# SPWF04SA-v1_0_0.net
KiCad netlist of a schematic drawn in EAGLE
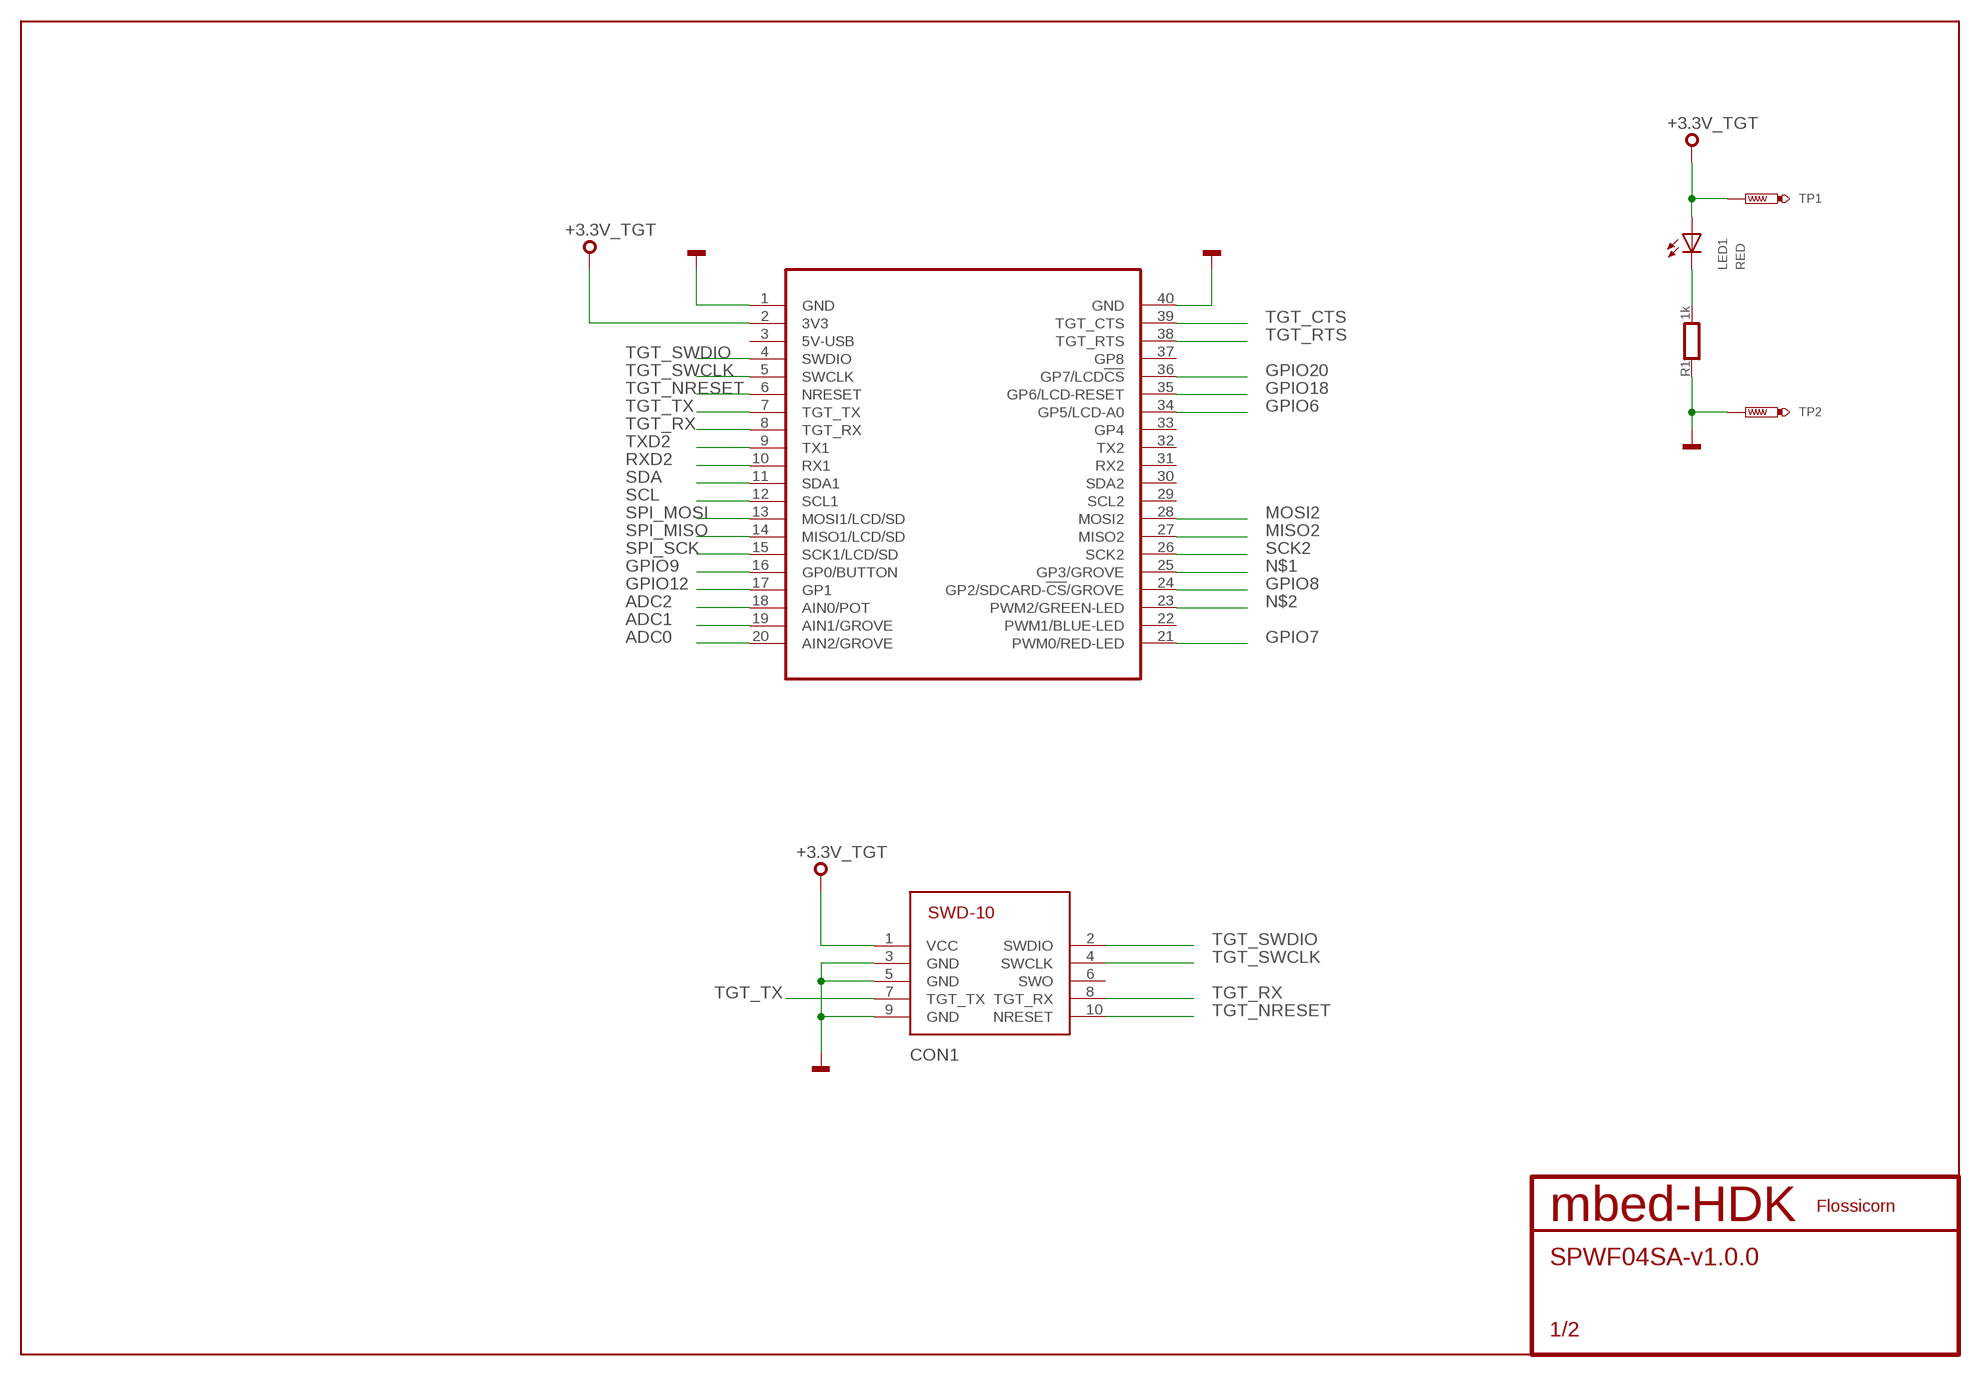
[diagram p0: schematic, sheet 1]
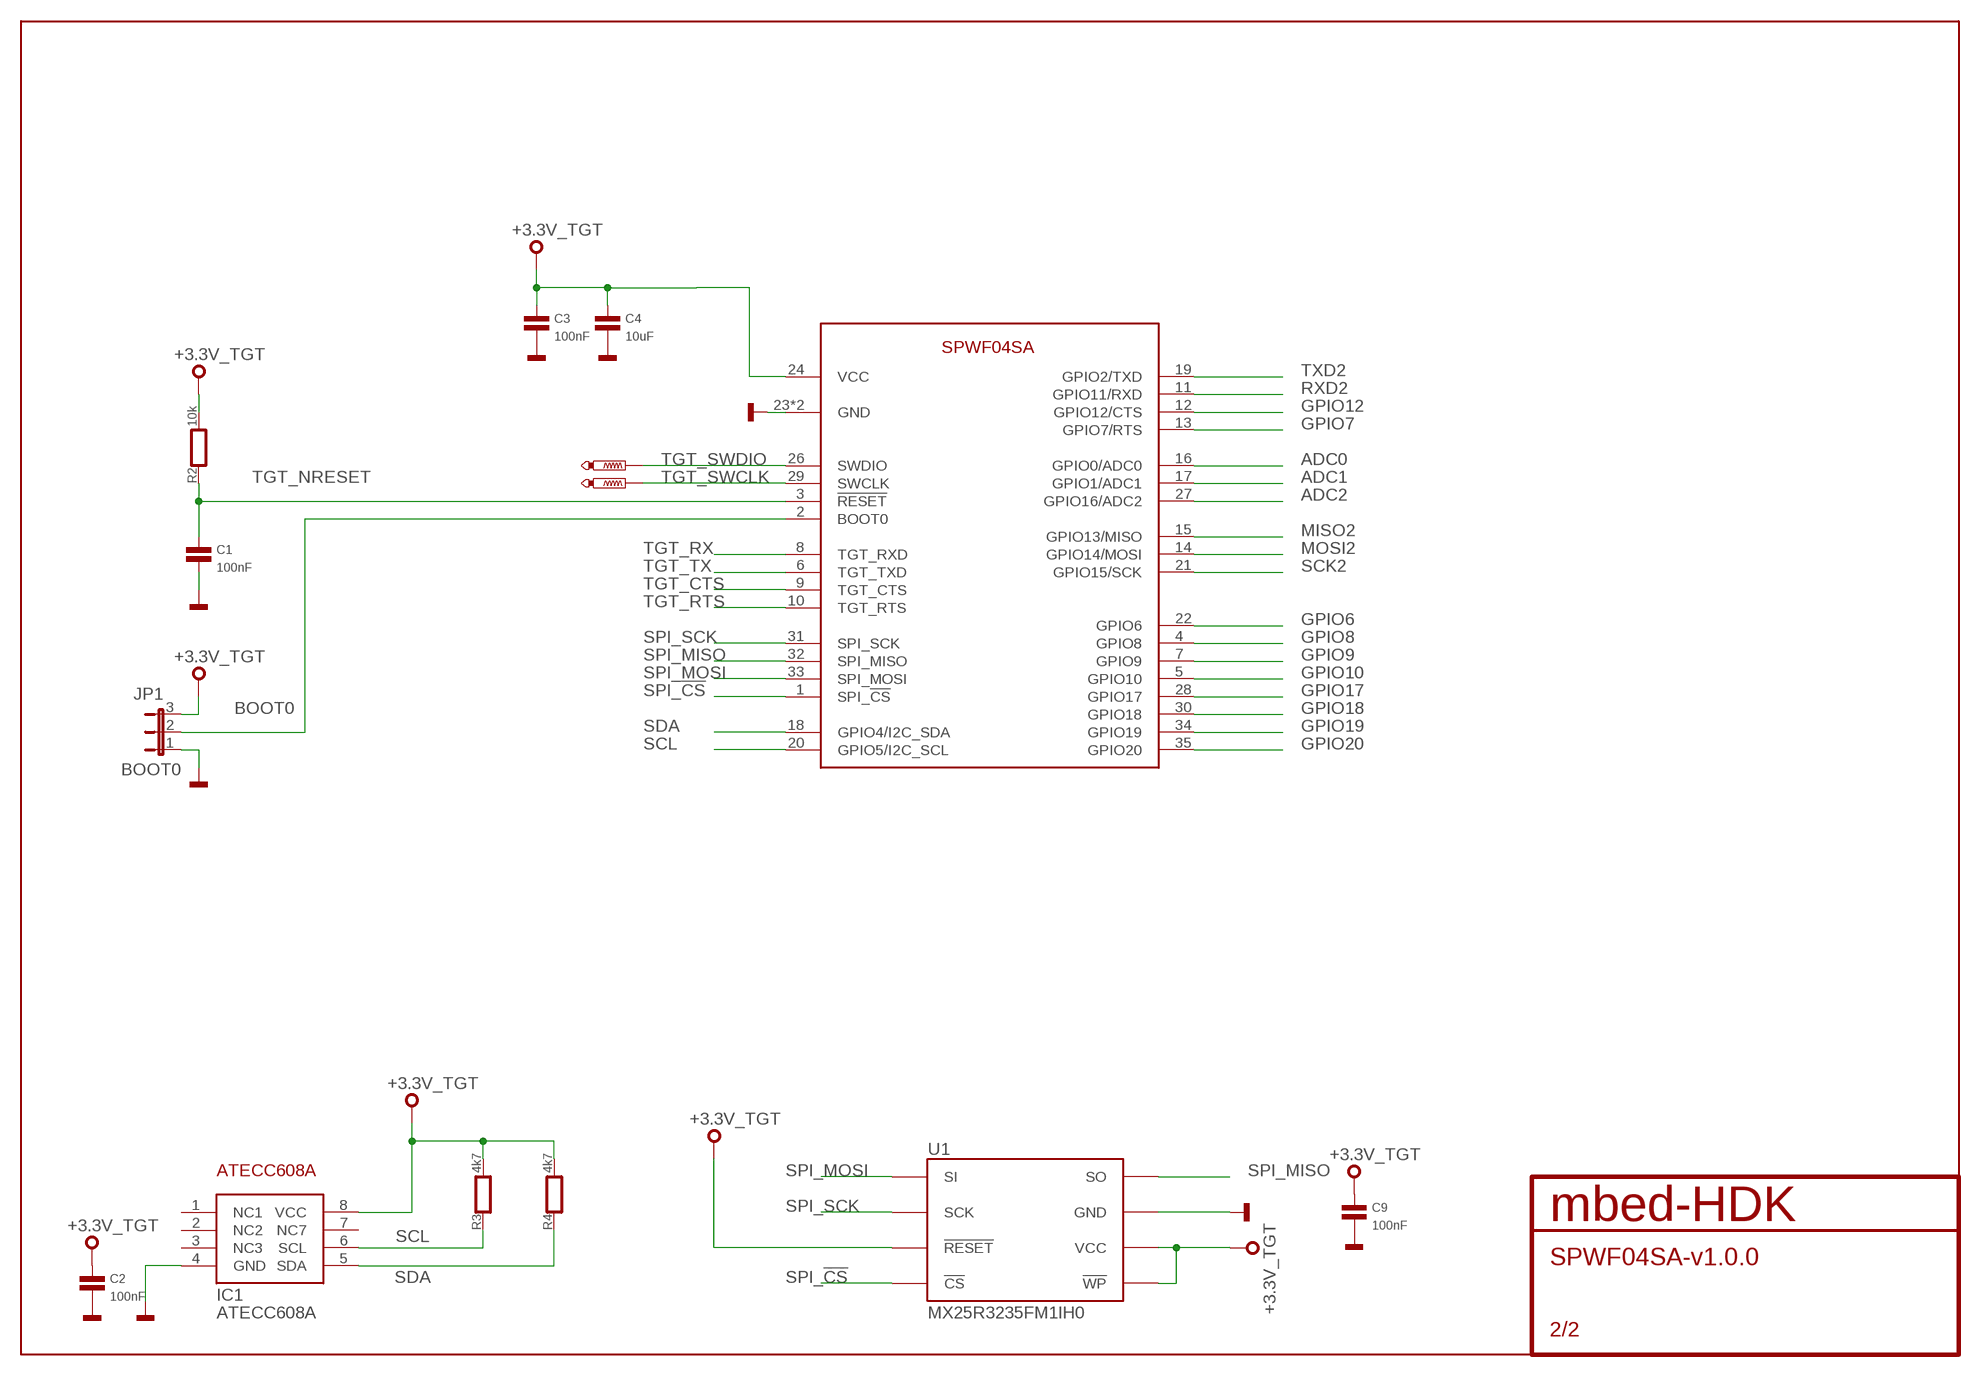
[diagram p1: schematic, sheet 2]

(export (version "E")
  (design (tool "Eeschema 10.0.6"))
  (components
    (comp (ref "C1")
      (value "100nF")
      (footprint "eagle-import:0603")
      (libsource (lib "eagle-import") (part "CAPACITOR0603"))
    )
    (comp (ref "C2")
      (value "100nF")
      (footprint "eagle-import:0603")
      (libsource (lib "eagle-import") (part "CAPACITOR0603"))
    )
    (comp (ref "C3")
      (value "100nF")
      (footprint "eagle-import:0603")
      (libsource (lib "eagle-import") (part "CAPACITOR0603"))
    )
    (comp (ref "C4")
      (value "10uF")
      (footprint "eagle-import:0603")
      (libsource (lib "eagle-import") (part "CAPACITOR0603"))
    )
    (comp (ref "C9")
      (value "100nF")
      (footprint "eagle-import:0603")
      (libsource (lib "eagle-import") (part "CAPACITOR0603"))
    )
    (comp (ref "IC1")
      (value "ATECC608A")
      (footprint "eagle-import:SO8")
      (libsource (lib "eagle-import") (part "ATECC608A"))
    )
    (comp (ref "JP1")
      (value "BOOT0")
      (footprint "eagle-import:JP2")
      (libsource (lib "eagle-import") (part "JP2E"))
    )
    (comp (ref "MOD2")
      (value "SPWF04SA")
      (footprint "eagle-import:SPWF04SA")
      (libsource (lib "eagle-import") (part "SPWF04SA"))
    )
    (comp (ref "R2")
      (value "10k")
      (footprint "eagle-import:0603")
      (libsource (lib "eagle-import") (part "RESISTOR0603"))
    )
    (comp (ref "R3")
      (value "4k7")
      (footprint "eagle-import:0603")
      (libsource (lib "eagle-import") (part "RESISTOR0603"))
    )
    (comp (ref "R4")
      (value "4k7")
      (footprint "eagle-import:0603")
      (libsource (lib "eagle-import") (part "RESISTOR0603"))
    )
    (comp (ref "TP3")
      (value "PTR1TP10R")
      (footprint "eagle-import:TP10R")
      (libsource (lib "eagle-import") (part "PTR1TP10R"))
    )
    (comp (ref "TP4")
      (value "PTR1TP10R")
      (footprint "eagle-import:TP10R")
      (libsource (lib "eagle-import") (part "PTR1TP10R"))
    )
    (comp (ref "U1")
      (value "MX25R3235FM1IH0")
      (footprint "eagle-import:SO8")
      (fields (field (name "MF") "Macronix"))
      (libsource (lib "eagle-import") (part "MX25R3235FM1IH0"))
    )
    (comp (ref "CON1")
      (value "SWD-10/TC2050_SMD")
      (footprint "eagle-import:FTSH-105-02")
      (libsource (lib "eagle-import") (part "SWD-10/TC2050_SMD"))
    )
    (comp (ref "LED1")
      (value "RED")
      (footprint "eagle-import:CHIPLED_0603")
      (fields (field (name "MF") "Wurth Electronics Inc"))
      (libsource (lib "eagle-import") (part "SMD_LED0603"))
    )
    (comp (ref "MOD1")
      (value "MODULE_DAUGHTER")
      (footprint "eagle-import:MODULE_DAUGHTER")
      (libsource (lib "eagle-import") (part "MODULE_DAUGHTER"))
    )
    (comp (ref "R1")
      (value "1k")
      (footprint "eagle-import:0603")
      (libsource (lib "eagle-import") (part "RESISTOR0603"))
    )
    (comp (ref "SS1")
      (value "FLOSSICORN0.5")
      (footprint "eagle-import:FLOSSICORN-0.5")
      (libsource (lib "eagle-import") (part "FLOSSICORN0.5"))
    )
    (comp (ref "TP1")
      (value "TEST-POINT-50R-PTH")
      (footprint "eagle-import:TP50-PTH")
      (libsource (lib "eagle-import") (part "TEST-POINT-50R-PTH"))
    )
    (comp (ref "TP2")
      (value "TEST-POINT-50R-PTH")
      (footprint "eagle-import:TP50-PTH")
      (libsource (lib "eagle-import") (part "TEST-POINT-50R-PTH"))
    )
  )
  (nets
    (net (code "1") (name "+3.3V_TGT") (class "Default")
      (node (ref "C2") (pin "1") (pinfunction "P$1_1") (pintype "passive"))
      (node (ref "C3") (pin "1") (pinfunction "P$1_1") (pintype "passive"))
      (node (ref "C4") (pin "1") (pinfunction "P$1_1") (pintype "passive"))
      (node (ref "C9") (pin "1") (pinfunction "P$1_1") (pintype "passive"))
      (node (ref "CON1") (pin "1") (pinfunction "VCC_1") (pintype "bidirectional"))
      (node (ref "IC1") (pin "8") (pinfunction "VCC_8") (pintype "bidirectional"))
      (node (ref "JP1") (pin "3") (pinfunction "3_3") (pintype "passive"))
      (node (ref "LED1") (pin "A") (pinfunction "A_A") (pintype "passive"))
      (node (ref "MOD1") (pin "2") (pinfunction "3V3_2") (pintype "bidirectional"))
      (node (ref "MOD2") (pin "24") (pinfunction "VCC_24") (pintype "bidirectional"))
      (node (ref "R2") (pin "2") (pinfunction "P$2_2") (pintype "passive"))
      (node (ref "R3") (pin "2") (pinfunction "P$2_2") (pintype "passive"))
      (node (ref "R4") (pin "2") (pinfunction "P$2_2") (pintype "passive"))
      (node (ref "TP1") (pin "TP") (pinfunction "TP_TP") (pintype "input"))
      (node (ref "U1") (pin "3") (pinfunction "~{WP}_3") (pintype "bidirectional"))
      (node (ref "U1") (pin "7") (pinfunction "~{RESET}_7") (pintype "bidirectional"))
      (node (ref "U1") (pin "8") (pinfunction "VCC_8") (pintype "bidirectional"))
    )
    (net (code "2") (name "ADC0") (class "Default")
      (node (ref "MOD1") (pin "20") (pinfunction "AIN2/GROVE_20") (pintype "bidirectional"))
      (node (ref "MOD2") (pin "16") (pinfunction "GPIO0/ADC0_16") (pintype "bidirectional"))
    )
    (net (code "3") (name "ADC1") (class "Default")
      (node (ref "MOD1") (pin "19") (pinfunction "AIN1/GROVE_19") (pintype "bidirectional"))
      (node (ref "MOD2") (pin "17") (pinfunction "GPIO1/ADC1_17") (pintype "bidirectional"))
    )
    (net (code "4") (name "ADC2") (class "Default")
      (node (ref "MOD1") (pin "18") (pinfunction "AIN0/POT_18") (pintype "bidirectional"))
      (node (ref "MOD2") (pin "27") (pinfunction "GPIO16/ADC2_27") (pintype "bidirectional"))
    )
    (net (code "5") (name "BOOT0") (class "Default")
      (node (ref "JP1") (pin "2") (pinfunction "2_2") (pintype "passive"))
      (node (ref "MOD2") (pin "2") (pinfunction "BOOT0_2") (pintype "bidirectional"))
    )
    (net (code "6") (name "GND") (class "Default")
      (node (ref "C1") (pin "2") (pinfunction "P$2_2") (pintype "passive"))
      (node (ref "C2") (pin "2") (pinfunction "P$2_2") (pintype "passive"))
      (node (ref "C3") (pin "2") (pinfunction "P$2_2") (pintype "passive"))
      (node (ref "C4") (pin "2") (pinfunction "P$2_2") (pintype "passive"))
      (node (ref "C9") (pin "2") (pinfunction "P$2_2") (pintype "passive"))
      (node (ref "CON1") (pin "3") (pinfunction "GND_3") (pintype "bidirectional"))
      (node (ref "CON1") (pin "5") (pinfunction "GND_5") (pintype "bidirectional"))
      (node (ref "CON1") (pin "9") (pinfunction "GND_9") (pintype "bidirectional"))
      (node (ref "IC1") (pin "4") (pinfunction "GND_4") (pintype "bidirectional"))
      (node (ref "JP1") (pin "1") (pinfunction "1_1") (pintype "passive"))
      (node (ref "MOD1") (pin "1") (pinfunction "GND_1") (pintype "bidirectional"))
      (node (ref "MOD1") (pin "40") (pinfunction "GND_40") (pintype "bidirectional"))
      (node (ref "MOD2") (pin "23") (pinfunction "GND_23") (pintype "bidirectional"))
      (node (ref "MOD2") (pin "25") (pinfunction "GND_25") (pintype "bidirectional"))
      (node (ref "R1") (pin "1") (pinfunction "P$1_1") (pintype "passive"))
      (node (ref "TP2") (pin "TP") (pinfunction "TP_TP") (pintype "input"))
      (node (ref "U1") (pin "4") (pinfunction "GND_4") (pintype "bidirectional"))
    )
    (net (code "7") (name "GPIO6") (class "Default")
      (node (ref "MOD1") (pin "34") (pinfunction "GP5/LCD-A0_34") (pintype "bidirectional"))
      (node (ref "MOD2") (pin "22") (pinfunction "GPIO6_22") (pintype "bidirectional"))
    )
    (net (code "8") (name "GPIO7") (class "Default")
      (node (ref "MOD1") (pin "21") (pinfunction "PWM0/RED-LED_21") (pintype "bidirectional"))
      (node (ref "MOD2") (pin "13") (pinfunction "GPIO7/RTS_13") (pintype "bidirectional"))
    )
    (net (code "9") (name "GPIO8") (class "Default")
      (node (ref "MOD1") (pin "24") (pinfunction "GP2/SDCARD-~{CS}/GROVE_24") (pintype "bidirectional"))
      (node (ref "MOD2") (pin "4") (pinfunction "GPIO8_4") (pintype "bidirectional"))
    )
    (net (code "10") (name "GPIO9") (class "Default")
      (node (ref "MOD1") (pin "16") (pinfunction "GP0/BUTTON_16") (pintype "bidirectional"))
      (node (ref "MOD2") (pin "7") (pinfunction "GPIO9_7") (pintype "bidirectional"))
    )
    (net (code "11") (name "GPIO10") (class "Default")
      (node (ref "MOD2") (pin "5") (pinfunction "GPIO10_5") (pintype "bidirectional"))
    )
    (net (code "12") (name "GPIO12") (class "Default")
      (node (ref "MOD1") (pin "17") (pinfunction "GP1_17") (pintype "bidirectional"))
      (node (ref "MOD2") (pin "12") (pinfunction "GPIO12/CTS_12") (pintype "bidirectional"))
    )
    (net (code "13") (name "GPIO17") (class "Default")
      (node (ref "MOD2") (pin "28") (pinfunction "GPIO17_28") (pintype "bidirectional"))
    )
    (net (code "14") (name "GPIO18") (class "Default")
      (node (ref "MOD1") (pin "35") (pinfunction "GP6/LCD-RESET_35") (pintype "bidirectional"))
      (node (ref "MOD2") (pin "30") (pinfunction "GPIO18_30") (pintype "bidirectional"))
    )
    (net (code "15") (name "GPIO19") (class "Default")
      (node (ref "MOD2") (pin "34") (pinfunction "GPIO19_34") (pintype "bidirectional"))
    )
    (net (code "16") (name "GPIO20") (class "Default")
      (node (ref "MOD1") (pin "36") (pinfunction "GP7/LCD~{CS}_36") (pintype "bidirectional"))
      (node (ref "MOD2") (pin "35") (pinfunction "GPIO20_35") (pintype "bidirectional"))
    )
    (net (code "17") (name "MISO2") (class "Default")
      (node (ref "MOD1") (pin "27") (pinfunction "MISO2_27") (pintype "bidirectional"))
      (node (ref "MOD2") (pin "15") (pinfunction "GPIO13/MISO_15") (pintype "bidirectional"))
    )
    (net (code "18") (name "MOSI2") (class "Default")
      (node (ref "MOD1") (pin "28") (pinfunction "MOSI2_28") (pintype "bidirectional"))
      (node (ref "MOD2") (pin "14") (pinfunction "GPIO14/MOSI_14") (pintype "bidirectional"))
    )
    (net (code "19") (name "N$1") (class "Default")
      (node (ref "MOD1") (pin "25") (pinfunction "GP3/GROVE_25") (pintype "bidirectional"))
    )
    (net (code "20") (name "N$2") (class "Default")
      (node (ref "MOD1") (pin "23") (pinfunction "PWM2/GREEN-LED_23") (pintype "bidirectional"))
    )
    (net (code "21") (name "Net-(R1-P$2)") (class "Default")
      (node (ref "LED1") (pin "C") (pinfunction "C_C") (pintype "passive"))
      (node (ref "R1") (pin "2") (pinfunction "P$2_2") (pintype "passive"))
    )
    (net (code "22") (name "RXD2") (class "Default")
      (node (ref "MOD1") (pin "10") (pinfunction "RX1_10") (pintype "bidirectional"))
      (node (ref "MOD2") (pin "11") (pinfunction "GPIO11/RXD_11") (pintype "bidirectional"))
    )
    (net (code "23") (name "SCK2") (class "Default")
      (node (ref "MOD1") (pin "26") (pinfunction "SCK2_26") (pintype "bidirectional"))
      (node (ref "MOD2") (pin "21") (pinfunction "GPIO15/SCK_21") (pintype "bidirectional"))
    )
    (net (code "24") (name "SCL") (class "Default")
      (node (ref "IC1") (pin "6") (pinfunction "SCL_6") (pintype "bidirectional"))
      (node (ref "MOD1") (pin "12") (pinfunction "SCL1_12") (pintype "bidirectional"))
      (node (ref "MOD2") (pin "20") (pinfunction "GPIO5/I2C_SCL_20") (pintype "bidirectional"))
      (node (ref "R3") (pin "1") (pinfunction "P$1_1") (pintype "passive"))
    )
    (net (code "25") (name "SDA") (class "Default")
      (node (ref "IC1") (pin "5") (pinfunction "SDA_5") (pintype "bidirectional"))
      (node (ref "MOD1") (pin "11") (pinfunction "SDA1_11") (pintype "bidirectional"))
      (node (ref "MOD2") (pin "18") (pinfunction "GPIO4/I2C_SDA_18") (pintype "bidirectional"))
      (node (ref "R4") (pin "1") (pinfunction "P$1_1") (pintype "passive"))
    )
    (net (code "26") (name "SPI_MISO") (class "Default")
      (node (ref "MOD1") (pin "14") (pinfunction "MISO1/LCD/SD_14") (pintype "bidirectional"))
      (node (ref "MOD2") (pin "32") (pinfunction "SPI_MISO_32") (pintype "bidirectional"))
      (node (ref "U1") (pin "2") (pinfunction "SO_2") (pintype "bidirectional"))
    )
    (net (code "27") (name "SPI_MOSI") (class "Default")
      (node (ref "MOD1") (pin "13") (pinfunction "MOSI1/LCD/SD_13") (pintype "bidirectional"))
      (node (ref "MOD2") (pin "33") (pinfunction "SPI_MOSI_33") (pintype "bidirectional"))
      (node (ref "U1") (pin "5") (pinfunction "SI_5") (pintype "bidirectional"))
    )
    (net (code "28") (name "SPI_SCK") (class "Default")
      (node (ref "MOD1") (pin "15") (pinfunction "SCK1/LCD/SD_15") (pintype "bidirectional"))
      (node (ref "MOD2") (pin "31") (pinfunction "SPI_SCK_31") (pintype "bidirectional"))
      (node (ref "U1") (pin "6") (pinfunction "SCK_6") (pintype "bidirectional"))
    )
    (net (code "29") (name "SPI_~{CS}") (class "Default")
      (node (ref "MOD2") (pin "1") (pinfunction "SPI_~{CS}_1") (pintype "bidirectional"))
      (node (ref "U1") (pin "1") (pinfunction "~{CS}_1") (pintype "bidirectional"))
    )
    (net (code "30") (name "TGT_CTS") (class "Default")
      (node (ref "MOD1") (pin "39") (pinfunction "TGT_CTS_39") (pintype "bidirectional"))
      (node (ref "MOD2") (pin "9") (pinfunction "TGT_CTS_9") (pintype "bidirectional"))
    )
    (net (code "31") (name "TGT_NRESET") (class "Default")
      (node (ref "C1") (pin "1") (pinfunction "P$1_1") (pintype "passive"))
      (node (ref "CON1") (pin "10") (pinfunction "NRESET_10") (pintype "bidirectional"))
      (node (ref "MOD1") (pin "6") (pinfunction "NRESET_6") (pintype "bidirectional"))
      (node (ref "MOD2") (pin "3") (pinfunction "~{RESET}_3") (pintype "bidirectional"))
      (node (ref "R2") (pin "1") (pinfunction "P$1_1") (pintype "passive"))
    )
    (net (code "32") (name "TGT_RTS") (class "Default")
      (node (ref "MOD1") (pin "38") (pinfunction "TGT_RTS_38") (pintype "bidirectional"))
      (node (ref "MOD2") (pin "10") (pinfunction "TGT_RTS_10") (pintype "bidirectional"))
    )
    (net (code "33") (name "TGT_RX") (class "Default")
      (node (ref "CON1") (pin "8") (pinfunction "TGT_RX_8") (pintype "bidirectional"))
      (node (ref "MOD1") (pin "8") (pinfunction "TGT_RX_8") (pintype "bidirectional"))
      (node (ref "MOD2") (pin "8") (pinfunction "TGT_RXD_8") (pintype "bidirectional"))
    )
    (net (code "34") (name "TGT_SWCLK") (class "Default")
      (node (ref "CON1") (pin "4") (pinfunction "SWCLK_4") (pintype "bidirectional"))
      (node (ref "MOD1") (pin "5") (pinfunction "SWCLK_5") (pintype "bidirectional"))
      (node (ref "MOD2") (pin "29") (pinfunction "SWCLK_29") (pintype "bidirectional"))
      (node (ref "TP4") (pin "TP") (pinfunction "TP_TP") (pintype "input"))
    )
    (net (code "35") (name "TGT_SWDIO") (class "Default")
      (node (ref "CON1") (pin "2") (pinfunction "SWDIO_2") (pintype "bidirectional"))
      (node (ref "MOD1") (pin "4") (pinfunction "SWDIO_4") (pintype "bidirectional"))
      (node (ref "MOD2") (pin "26") (pinfunction "SWDIO_26") (pintype "bidirectional"))
      (node (ref "TP3") (pin "TP") (pinfunction "TP_TP") (pintype "input"))
    )
    (net (code "36") (name "TGT_TX") (class "Default")
      (node (ref "CON1") (pin "7") (pinfunction "TGT_TX_7") (pintype "bidirectional"))
      (node (ref "MOD1") (pin "7") (pinfunction "TGT_TX_7") (pintype "bidirectional"))
      (node (ref "MOD2") (pin "6") (pinfunction "TGT_TXD_6") (pintype "bidirectional"))
    )
    (net (code "37") (name "TXD2") (class "Default")
      (node (ref "MOD1") (pin "9") (pinfunction "TX1_9") (pintype "bidirectional"))
      (node (ref "MOD2") (pin "19") (pinfunction "GPIO2/TXD_19") (pintype "bidirectional"))
    )
    (net (code "38") (name "unconnected-(CON1-SWO-Pad6)") (class "Default")
      (node (ref "CON1") (pin "6") (pinfunction "SWO_6") (pintype "bidirectional"))
    )
    (net (code "39") (name "unconnected-(IC1-NC1-Pad1)") (class "Default")
      (node (ref "IC1") (pin "1") (pinfunction "NC1_1") (pintype "bidirectional"))
    )
    (net (code "40") (name "unconnected-(IC1-NC2-Pad2)") (class "Default")
      (node (ref "IC1") (pin "2") (pinfunction "NC2_2") (pintype "bidirectional"))
    )
    (net (code "41") (name "unconnected-(IC1-NC3-Pad3)") (class "Default")
      (node (ref "IC1") (pin "3") (pinfunction "NC3_3") (pintype "bidirectional"))
    )
    (net (code "42") (name "unconnected-(IC1-NC7-Pad7)") (class "Default")
      (node (ref "IC1") (pin "7") (pinfunction "NC7_7") (pintype "bidirectional"))
    )
    (net (code "43") (name "unconnected-(MOD1-5V-USB-Pad3)") (class "Default")
      (node (ref "MOD1") (pin "3") (pinfunction "5V-USB_3") (pintype "bidirectional"))
    )
    (net (code "44") (name "unconnected-(MOD1-GP4-Pad33)") (class "Default")
      (node (ref "MOD1") (pin "33") (pinfunction "GP4_33") (pintype "bidirectional"))
    )
    (net (code "45") (name "unconnected-(MOD1-GP8-Pad37)") (class "Default")
      (node (ref "MOD1") (pin "37") (pinfunction "GP8_37") (pintype "bidirectional"))
    )
    (net (code "46") (name "unconnected-(MOD1-PWM1{slash}BLUE-LED-Pad22)") (class "Default")
      (node (ref "MOD1") (pin "22") (pinfunction "PWM1/BLUE-LED_22") (pintype "bidirectional"))
    )
    (net (code "47") (name "unconnected-(MOD1-RX2-Pad31)") (class "Default")
      (node (ref "MOD1") (pin "31") (pinfunction "RX2_31") (pintype "bidirectional"))
    )
    (net (code "48") (name "unconnected-(MOD1-SCL2-Pad29)") (class "Default")
      (node (ref "MOD1") (pin "29") (pinfunction "SCL2_29") (pintype "bidirectional"))
    )
    (net (code "49") (name "unconnected-(MOD1-SDA2-Pad30)") (class "Default")
      (node (ref "MOD1") (pin "30") (pinfunction "SDA2_30") (pintype "bidirectional"))
    )
    (net (code "50") (name "unconnected-(MOD1-TX2-Pad32)") (class "Default")
      (node (ref "MOD1") (pin "32") (pinfunction "TX2_32") (pintype "bidirectional"))
    )
  )
)
